# BackBoomSchem.net
KiCad netlist of a schematic drawn in Altium Designer
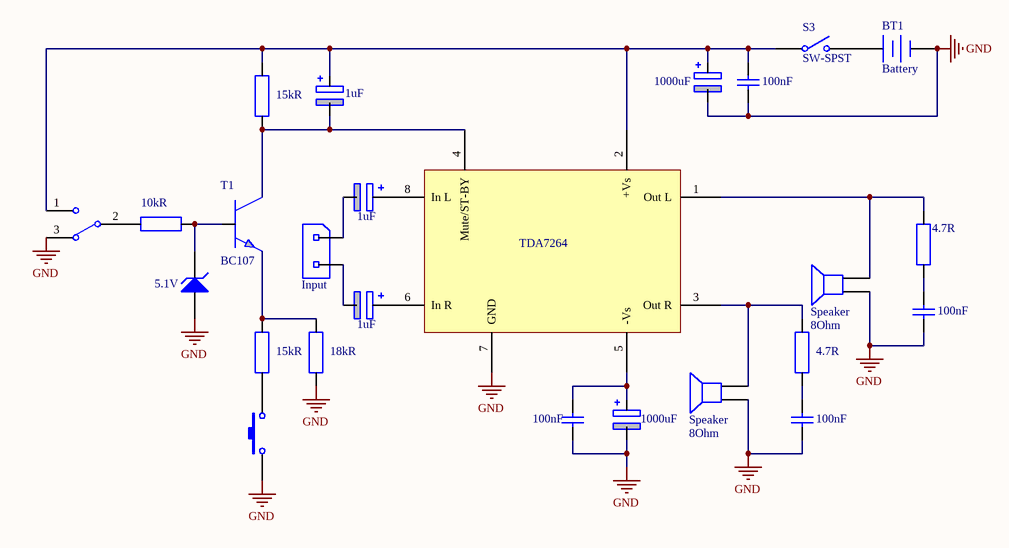
[diagram p0: BackBoomSchem.SchDoc]

(export (version "E")
  (design (tool "Eeschema 10.0.6"))
  (components
    (comp (ref "BT1")
      (value "Battery")
      (footprint "BAT-2")
      (description "Multicell Battery")
      (fields (field (name "PUBLISHER") "Altium Limited"))
      (libsource (lib "Miscellaneous Devices") (part "Battery"))
    )
    (comp (ref "C1")
      (value "1uF")
      (footprint "cap 48 pol (.46/.2/.6/125/36)")
      (description "elektrolytische condensator axiaal 0.47uF/63V")
      (fields (field (name "PART NUMBER") "CECA0.47uF/63V") (field (name "Comment") "Cap"))
      (libsource (lib "CDE_Library") (part "CECA0.47uF/63V"))
    )
    (comp (ref "C2")
      (value "1uF")
      (footprint "cap 48 pol (.46/.2/.6/125/36)")
      (description "elektrolytische condensator axiaal 0.47uF/63V")
      (fields (field (name "PART NUMBER") "CECA0.47uF/63V") (field (name "Comment") "Cap"))
      (libsource (lib "CDE_Library") (part "CECA0.47uF/63V"))
    )
    (comp (ref "C3")
      (value "1uF")
      (footprint "cap 48 pol (.46/.2/.6/125/36)")
      (description "elektrolytische condensator axiaal 0.47uF/63V")
      (fields (field (name "PART NUMBER") "CECA0.47uF/63V") (field (name "Comment") "Cap"))
      (libsource (lib "CDE_Library") (part "CECA0.47uF/63V"))
    )
    (comp (ref "C4")
      (value "1000uF")
      (footprint "cap 48 pol (.46/.2/.6/125/36)")
      (description "elektrolytische condensator axiaal 0.47uF/63V")
      (fields (field (name "PART NUMBER") "CECA0.47uF/63V") (field (name "Comment") "Cap"))
      (libsource (lib "CDE_Library") (part "CECA0.47uF/63V"))
    )
    (comp (ref "C5")
      (value "100nF")
      (footprint "RAD-0.3")
      (description "Capacitor")
      (fields (field (name "PUBLISHER") "Altium Limited"))
      (libsource (lib "Miscellaneous Devices") (part "Cap"))
    )
    (comp (ref "C6")
      (value "1000uF")
      (footprint "cap 48 pol (.46/.2/.6/125/36)")
      (description "elektrolytische condensator axiaal 0.47uF/63V")
      (fields (field (name "PART NUMBER") "CECA0.47uF/63V") (field (name "Comment") "Cap"))
      (libsource (lib "CDE_Library") (part "CECA0.47uF/63V"))
    )
    (comp (ref "C7")
      (value "100nF")
      (footprint "RAD-0.3")
      (description "Capacitor")
      (fields (field (name "Comment") "Cap") (field (name "PUBLISHER") "Altium Limited"))
      (libsource (lib "Miscellaneous Devices") (part "Cap"))
    )
    (comp (ref "C8")
      (value "100nF")
      (footprint "RAD-0.3")
      (description "Capacitor")
      (fields (field (name "Comment") "Cap") (field (name "PUBLISHER") "Altium Limited"))
      (libsource (lib "Miscellaneous Devices") (part "Cap"))
    )
    (comp (ref "C9")
      (value "100nF")
      (footprint "RAD-0.3")
      (description "Capacitor")
      (fields (field (name "Comment") "Cap") (field (name "PUBLISHER") "Altium Limited"))
      (libsource (lib "Miscellaneous Devices") (part "Cap"))
    )
    (comp (ref "D1")
      (value "5.1V")
      (footprint "DIODE-0.7")
      (description "Zener Diode")
      (fields (field (name "Comment") "D Zener") (field (name "PUBLISHER") "Altium Limited"))
      (libsource (lib "Miscellaneous Devices") (part "D Zener"))
    )
    (comp (ref "In")
      (value "Input")
      (footprint "hdr 1x2")
      (description "pcb header recht 1x2  pitch 100mil")
      (fields (field (name "PART NUMBER") "CON HDR 1x2"))
      (libsource (lib "CDE_Library") (part "CON HDR 1x2"))
    )
    (comp (ref "LS_L")
      (value "Speaker")
      (footprint "PIN2")
      (description "Loudspeaker")
      (fields (field (name "INTERNAL RESISTANCE") "8Ohm") (field (name "PUBLISHER") "Altium Limited"))
      (libsource (lib "Miscellaneous Devices") (part "Speaker"))
    )
    (comp (ref "LS_R")
      (value "Speaker")
      (footprint "PIN2")
      (description "Loudspeaker")
      (fields (field (name "INTERNAL RESISTANCE") "8Ohm") (field (name "PUBLISHER") "Altium Limited"))
      (libsource (lib "Miscellaneous Devices") (part "Speaker"))
    )
    (comp (ref "R1")
      (value "10kR")
      (footprint "ws 0.6W H")
      (description "weerstand 0R2 0.6W")
      (fields (field (name "Comment") "Res"))
      (libsource (lib "CDE_Library") (part "0R2"))
    )
    (comp (ref "R2")
      (value "15kR")
      (footprint "ws 0.6W H")
      (description "weerstand 0R2 0.6W")
      (fields (field (name "Comment") "Res"))
      (libsource (lib "CDE_Library") (part "0R2"))
    )
    (comp (ref "R3")
      (value "18kR")
      (footprint "ws 0.6W H")
      (description "weerstand 0R2 0.6W")
      (fields (field (name "Comment") "Res"))
      (libsource (lib "CDE_Library") (part "0R2"))
    )
    (comp (ref "R4")
      (value "15kR")
      (footprint "ws 0.6W H")
      (description "weerstand 0R2 0.6W")
      (fields (field (name "Comment") "Res"))
      (libsource (lib "CDE_Library") (part "0R2"))
    )
    (comp (ref "R5")
      (value "4.7R")
      (footprint "ws 0.6W H")
      (description "weerstand 0R2 0.6W")
      (fields (field (name "Comment") "Res"))
      (libsource (lib "CDE_Library") (part "0R2"))
    )
    (comp (ref "R6")
      (value "4.7R")
      (footprint "ws 0.6W H")
      (description "weerstand 0R2 0.6W")
      (fields (field (name "Comment") "Res"))
      (libsource (lib "CDE_Library") (part "0R2"))
    )
    (comp (ref "S1")
      (value "SW-SPDT")
      (footprint "TL36WW15050")
      (description "SPDT Subminiature Toggle Switch, Right Angle Mounting, Vertical Actuation")
      (fields (field (name "PUBLISHER") "Altium Limited"))
      (libsource (lib "Miscellaneous Devices") (part "SW-SPDT"))
    )
    (comp (ref "S2")
      (value "SW-PB")
      (footprint "SPST-2")
      (description "Switch")
      (fields (field (name "PUBLISHER") "Altium Limited"))
      (libsource (lib "Miscellaneous Devices") (part "SW-PB"))
    )
    (comp (ref "S3")
      (value "SW-SPST")
      (footprint "SPST-2")
      (description "Single-Pole, Single-Throw Switch")
      (fields (field (name "PUBLISHER") "Altium Limited"))
      (libsource (lib "Miscellaneous Devices") (part "SW-SPST"))
    )
    (comp (ref "T1")
      (value "BC107")
      (footprint "TO-18")
      (description "NPN transistor")
      (libsource (lib "CDE_Library") (part "BC107"))
    )
    (comp (ref "TDA7264")
      (value "TDA7264 stereo audio amplifier")
      (footprint "MultiWatt8")
      (description "25 W + 25 W stereo amplifier with mute and standby")
      (libsource (lib "TomSchLib") (part "TDA7264 stereo audio amplifier"))
    )
  )
  (nets
    (net (code "1") (name "GND") (class "Default")
      (node (ref "BT1") (pin "2") (pinfunction "-_2") (pintype "passive"))
      (node (ref "C4") (pin "2") (pintype "passive"))
      (node (ref "C5") (pin "1") (pinfunction "1_1") (pintype "passive"))
      (node (ref "C6") (pin "2") (pintype "passive"))
      (node (ref "C7") (pin "1") (pinfunction "1_1") (pintype "passive"))
      (node (ref "C8") (pin "1") (pinfunction "1_1") (pintype "passive"))
      (node (ref "C9") (pin "1") (pinfunction "1_1") (pintype "passive"))
      (node (ref "D1") (pin "1") (pinfunction "A_1") (pintype "passive"))
      (node (ref "LS_L") (pin "1") (pinfunction "1_1") (pintype "passive"))
      (node (ref "LS_R") (pin "1") (pinfunction "1_1") (pintype "passive"))
      (node (ref "R3") (pin "1") (pintype "passive"))
      (node (ref "S1") (pin "3") (pinfunction "3_3") (pintype "passive"))
      (node (ref "S2") (pin "1") (pinfunction "1_1") (pintype "passive"))
      (node (ref "TDA7264") (pin "7") (pinfunction "GND_7") (pintype "passive"))
    )
    (net (code "2") (name "Net-(BT1-+)") (class "Default")
      (node (ref "BT1") (pin "1") (pinfunction "+_1") (pintype "passive"))
      (node (ref "S3") (pin "2") (pinfunction "NO_2") (pintype "passive"))
    )
    (net (code "3") (name "Net-(C1-Pad2)") (class "Default")
      (node (ref "C1") (pin "2") (pintype "passive"))
      (node (ref "In") (pin "1") (pintype "passive"))
    )
    (net (code "4") (name "Net-(C2-Pad2)") (class "Default")
      (node (ref "C2") (pin "2") (pintype "passive"))
      (node (ref "In") (pin "2") (pintype "passive"))
    )
    (net (code "5") (name "Net-(C8-Pad2)") (class "Default")
      (node (ref "C8") (pin "2") (pinfunction "2_2") (pintype "passive"))
      (node (ref "R5") (pin "2") (pintype "passive"))
    )
    (net (code "6") (name "Net-(C9-Pad2)") (class "Default")
      (node (ref "C9") (pin "2") (pinfunction "2_2") (pintype "passive"))
      (node (ref "R6") (pin "1") (pintype "passive"))
    )
    (net (code "7") (name "Net-(D1-K)") (class "Default")
      (node (ref "D1") (pin "2") (pinfunction "K_2") (pintype "passive"))
      (node (ref "R1") (pin "1") (pintype "passive"))
      (node (ref "T1") (pin "2") (pintype "passive"))
    )
    (net (code "8") (name "Net-(R1-Pad2)") (class "Default")
      (node (ref "R1") (pin "2") (pintype "passive"))
      (node (ref "S1") (pin "2") (pinfunction "2_2") (pintype "passive"))
    )
    (net (code "9") (name "Net-(R3-Pad2)") (class "Default")
      (node (ref "R3") (pin "2") (pintype "passive"))
      (node (ref "R4") (pin "2") (pintype "passive"))
      (node (ref "T1") (pin "1") (pintype "passive"))
    )
    (net (code "10") (name "Net-(R4-Pad1)") (class "Default")
      (node (ref "R4") (pin "1") (pintype "passive"))
      (node (ref "S2") (pin "2") (pinfunction "2_2") (pintype "passive"))
    )
    (net (code "11") (name "Net-(S3-COMMON)") (class "Default")
      (node (ref "C3") (pin "1") (pintype "passive"))
      (node (ref "C4") (pin "1") (pintype "passive"))
      (node (ref "C5") (pin "2") (pinfunction "2_2") (pintype "passive"))
      (node (ref "R2") (pin "2") (pintype "passive"))
      (node (ref "S1") (pin "1") (pinfunction "1_1") (pintype "passive"))
      (node (ref "S3") (pin "1") (pinfunction "COMMON_1") (pintype "passive"))
      (node (ref "TDA7264") (pin "2") (pinfunction "+Vs_2") (pintype "passive"))
    )
    (net (code "12") (name "Net-(TDA7264--Vs)") (class "Default")
      (node (ref "C6") (pin "1") (pintype "passive"))
      (node (ref "C7") (pin "2") (pinfunction "2_2") (pintype "passive"))
      (node (ref "TDA7264") (pin "5") (pinfunction "-Vs_5") (pintype "passive"))
    )
    (net (code "13") (name "Net-(TDA7264-In_L)") (class "Default")
      (node (ref "C1") (pin "1") (pintype "passive"))
      (node (ref "TDA7264") (pin "8") (pinfunction "In_L_8") (pintype "passive"))
    )
    (net (code "14") (name "Net-(TDA7264-In_R)") (class "Default")
      (node (ref "C2") (pin "1") (pintype "passive"))
      (node (ref "TDA7264") (pin "6") (pinfunction "In_R_6") (pintype "passive"))
    )
    (net (code "15") (name "Net-(TDA7264-Mute{slash}ST-BY)") (class "Default")
      (node (ref "C3") (pin "2") (pintype "passive"))
      (node (ref "R2") (pin "1") (pintype "passive"))
      (node (ref "T1") (pin "3") (pintype "passive"))
      (node (ref "TDA7264") (pin "4") (pinfunction "Mute/ST-BY_4") (pintype "passive"))
    )
    (net (code "16") (name "Net-(TDA7264-Out_L)") (class "Default")
      (node (ref "LS_L") (pin "2") (pinfunction "2_2") (pintype "passive"))
      (node (ref "R5") (pin "1") (pintype "passive"))
      (node (ref "TDA7264") (pin "1") (pinfunction "Out_L_1") (pintype "passive"))
    )
    (net (code "17") (name "Net-(TDA7264-Out_R)") (class "Default")
      (node (ref "LS_R") (pin "2") (pinfunction "2_2") (pintype "passive"))
      (node (ref "R6") (pin "2") (pintype "passive"))
      (node (ref "TDA7264") (pin "3") (pinfunction "Out_R_3") (pintype "passive"))
    )
  )
)
